# RGB_LED_BUCK_Converters.net
KiCad netlist of a schematic drawn in Altium Designer
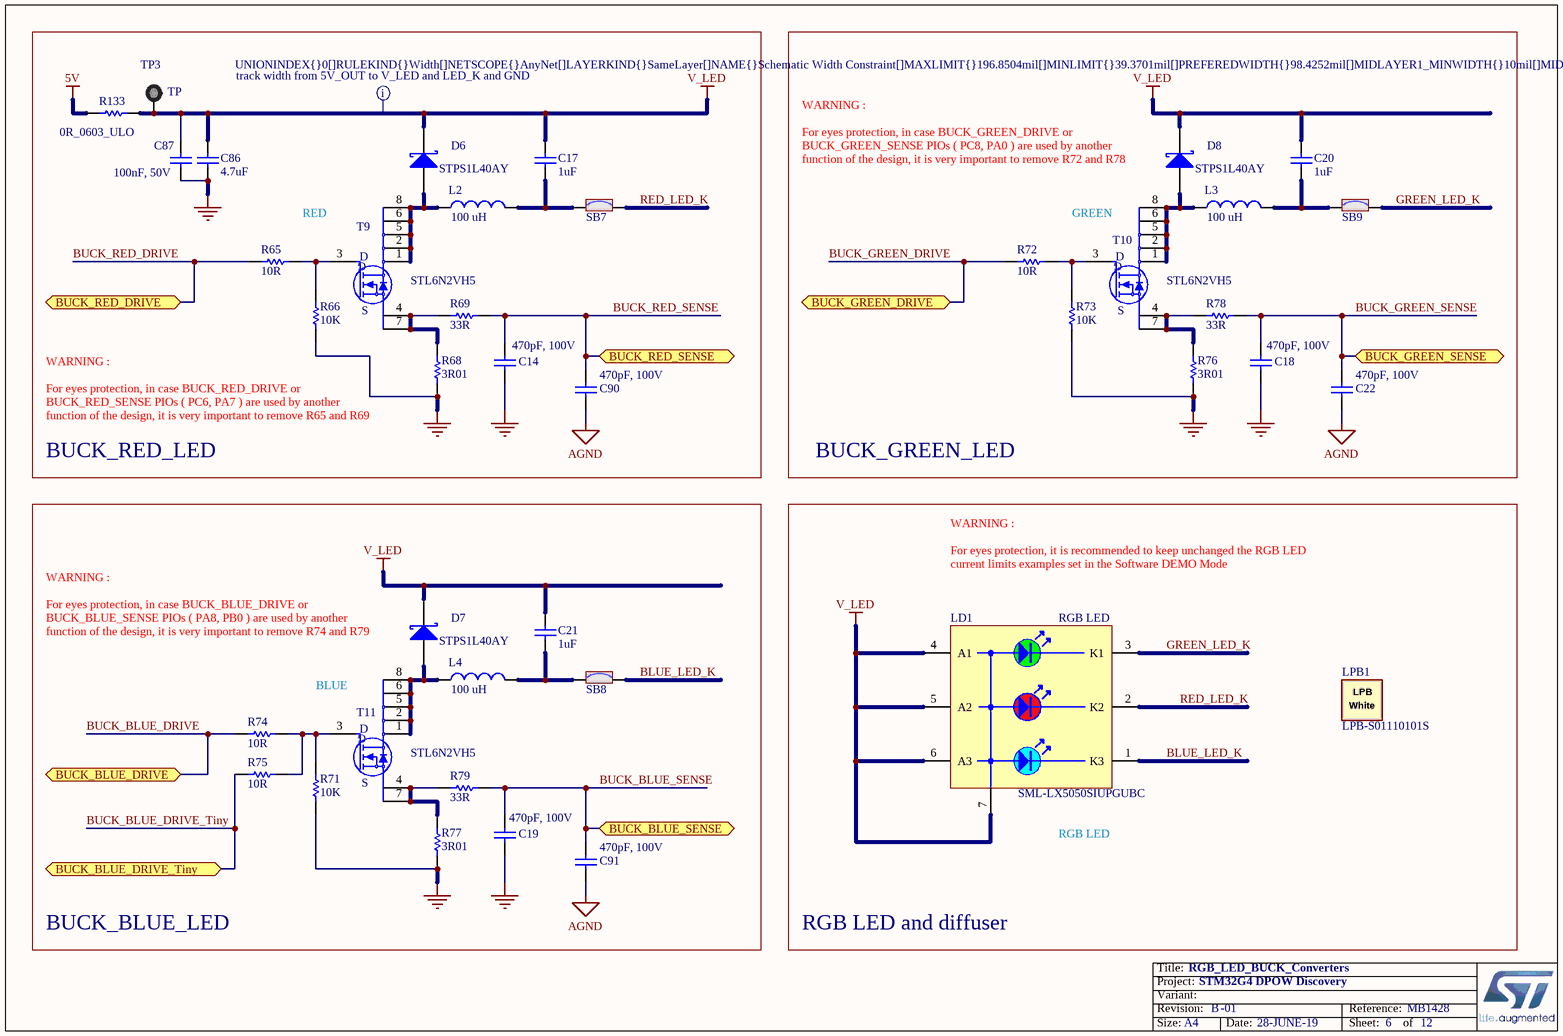
[diagram p0: RGB_LED_BUCK_Converters.SchDoc]

(export (version "E")
  (design (tool "Eeschema 10.0.6"))
  (components
    (comp (ref "C14")
      (value "470pF, 100V")
      (footprint "C0603_H0P8")
      (description "Capacitor, MLCC, 470pF, 100V, X7R, 10%, 0603, T=0.8mm")
      (fields
        (field (name "INTERNAL_PART_NUMBER") "MCD-01731")
        (field (name "MANUFACTURER_PART_NUMBER") "CC0603KRX7R0BB471")
        (field (name "PROVIDED_BY") "SUBCO")
      )
      (libsource (lib "MCD_PARTS_database") (part "Capacitor"))
    )
    (comp (ref "C17")
      (value "1uF")
      (footprint "C0805_H0P85")
      (description "Capacitor, MLCC, 1uF, 16V, X5R, 10%, 0805, T=0.85mm")
      (fields
        (field (name "INTERNAL_PART_NUMBER") "MCD-01550")
        (field (name "MANUFACTURER_PART_NUMBER") "CC0805KRX5R7BB105")
        (field (name "PROVIDED_BY") "SUBCO")
      )
      (libsource (lib "MCD_PARTS_database") (part "Capacitor"))
    )
    (comp (ref "C18")
      (value "470pF, 100V")
      (footprint "C0603_H0P8")
      (description "Capacitor, MLCC, 470pF, 100V, X7R, 10%, 0603, T=0.8mm")
      (fields
        (field (name "INTERNAL_PART_NUMBER") "MCD-01731")
        (field (name "MANUFACTURER_PART_NUMBER") "CC0603KRX7R0BB471")
        (field (name "PROVIDED_BY") "SUBCO")
      )
      (libsource (lib "MCD_PARTS_database") (part "Capacitor"))
    )
    (comp (ref "C19")
      (value "470pF, 100V")
      (footprint "C0603_H0P8")
      (description "Capacitor, MLCC, 470pF, 100V, X7R, 10%, 0603, T=0.8mm")
      (fields
        (field (name "INTERNAL_PART_NUMBER") "MCD-01731")
        (field (name "MANUFACTURER_PART_NUMBER") "CC0603KRX7R0BB471")
        (field (name "PROVIDED_BY") "SUBCO")
      )
      (libsource (lib "MCD_PARTS_database") (part "Capacitor"))
    )
    (comp (ref "C20")
      (value "1uF")
      (footprint "C0805_H0P85")
      (description "Capacitor, MLCC, 1uF, 16V, X5R, 10%, 0805, T=0.85mm")
      (fields
        (field (name "INTERNAL_PART_NUMBER") "MCD-01550")
        (field (name "MANUFACTURER_PART_NUMBER") "CC0805KRX5R7BB105")
        (field (name "PROVIDED_BY") "SUBCO")
      )
      (libsource (lib "MCD_PARTS_database") (part "Capacitor"))
    )
    (comp (ref "C21")
      (value "1uF")
      (footprint "C0805_H0P85")
      (description "Capacitor, MLCC, 1uF, 16V, X5R, 10%, 0805, T=0.85mm")
      (fields
        (field (name "INTERNAL_PART_NUMBER") "MCD-01550")
        (field (name "MANUFACTURER_PART_NUMBER") "CC0805KRX5R7BB105")
        (field (name "PROVIDED_BY") "SUBCO")
      )
      (libsource (lib "MCD_PARTS_database") (part "Capacitor"))
    )
    (comp (ref "C22")
      (value "470pF, 100V")
      (footprint "C0603_H0P8")
      (description "Capacitor, MLCC, 470pF, 100V, X7R, 10%, 0603, T=0.8mm")
      (fields
        (field (name "INTERNAL_PART_NUMBER") "MCD-01731")
        (field (name "MANUFACTURER_PART_NUMBER") "CC0603KRX7R0BB471")
        (field (name "PROVIDED_BY") "SUBCO")
      )
      (libsource (lib "MCD_PARTS_database") (part "Capacitor"))
    )
    (comp (ref "C86")
      (value "4.7uF")
      (footprint "C0603")
      (description "Capacitor, MLCC, 4.7uF, 16V, X5R, 10%, 0603, T=0.8mm")
      (fields
        (field (name "INTERNAL_PART_NUMBER") "MCD-00009")
        (field (name "MANUFACTURER_PART_NUMBER") "CC0603KRX5R7BB475")
        (field (name "PROVIDED_BY") "SUBCO")
      )
      (libsource (lib "MCD_PARTS_database") (part "Capacitor"))
    )
    (comp (ref "C87")
      (value "100nF, 50V")
      (footprint "C0805_H0P85")
      (description "Capacitor, MLCC, 100nF, 50V, X7R, 10%, 0805, T=0,85mm")
      (fields
        (field (name "INTERNAL_PART_NUMBER") "MCD-01525")
        (field (name "MANUFACTURER_PART_NUMBER") "CC0805KRX7R9BB104")
        (field (name "PROVIDED_BY") "SUBCO")
      )
      (libsource (lib "MCD_PARTS_database") (part "Capacitor"))
    )
    (comp (ref "C90")
      (value "470pF, 100V")
      (footprint "C0603_H0P8")
      (description "Capacitor, MLCC, 470pF, 100V, X7R, 10%, 0603, T=0.8mm")
      (fields
        (field (name "INTERNAL_PART_NUMBER") "MCD-01731")
        (field (name "MANUFACTURER_PART_NUMBER") "CC0603KRX7R0BB471")
        (field (name "PROVIDED_BY") "SUBCO")
      )
      (libsource (lib "MCD_PARTS_database") (part "Capacitor"))
    )
    (comp (ref "C91")
      (value "470pF, 100V")
      (footprint "C0603_H0P8")
      (description "Capacitor, MLCC, 470pF, 100V, X7R, 10%, 0603, T=0.8mm")
      (fields
        (field (name "INTERNAL_PART_NUMBER") "MCD-01731")
        (field (name "MANUFACTURER_PART_NUMBER") "CC0603KRX7R0BB471")
        (field (name "PROVIDED_BY") "SUBCO")
      )
      (libsource (lib "MCD_PARTS_database") (part "Capacitor"))
    )
    (comp (ref "D6")
      (value "STPS1L40AY")
      (footprint "DIO_SMA_1A_2K")
      (description "Low Drop power Schottky rectifier(1A, 40V, 0.37 V)")
      (fields
        (field (name "INTERNAL_PART_NUMBER") "MCD-00606")
        (field (name "MANUFACTURER") "STMICROELECTRONICS")
        (field (name "PROVIDED_BY") "SUBCO with ST control")
      )
      (libsource (lib "MCD_PARTS_database") (part "SCHOTTKY"))
    )
    (comp (ref "D7")
      (value "STPS1L40AY")
      (footprint "DIO_SMA_1A_2K")
      (description "Low Drop power Schottky rectifier(1A, 40V, 0.37 V)")
      (fields
        (field (name "INTERNAL_PART_NUMBER") "MCD-00606")
        (field (name "MANUFACTURER") "STMICROELECTRONICS")
        (field (name "PROVIDED_BY") "SUBCO with ST control")
      )
      (libsource (lib "MCD_PARTS_database") (part "SCHOTTKY"))
    )
    (comp (ref "D8")
      (value "STPS1L40AY")
      (footprint "DIO_SMA_1A_2K")
      (description "Low Drop power Schottky rectifier(1A, 40V, 0.37 V)")
      (fields
        (field (name "INTERNAL_PART_NUMBER") "MCD-00606")
        (field (name "MANUFACTURER") "STMICROELECTRONICS")
        (field (name "PROVIDED_BY") "SUBCO with ST control")
      )
      (libsource (lib "MCD_PARTS_database") (part "SCHOTTKY"))
    )
    (comp (ref "L2")
      (value "100 uH")
      (footprint "IND_SUNLORD_SWPA5040S")
      (description "SMD Wire wound power inductor, 100uH, 20%, Isat 0.9A, 560mohm, 5.0x5.0x4.0mm")
      (fields
        (field (name "INTERNAL_PART_NUMBER") "MCD-01734")
        (field (name "MANUFACTURER_PART_NUMBER") "SWPA5040S101MT")
        (field (name "PROVIDED_BY") "SUBCO")
      )
      (libsource (lib "MCD_PARTS_database") (part "Inductor"))
    )
    (comp (ref "L3")
      (value "100 uH")
      (footprint "IND_SUNLORD_SWPA5040S")
      (description "SMD Wire wound power inductor, 100uH, 20%, Isat 0.9A, 560mohm, 5.0x5.0x4.0mm")
      (fields
        (field (name "INTERNAL_PART_NUMBER") "MCD-01734")
        (field (name "MANUFACTURER_PART_NUMBER") "SWPA5040S101MT")
        (field (name "PROVIDED_BY") "SUBCO")
      )
      (libsource (lib "MCD_PARTS_database") (part "Inductor"))
    )
    (comp (ref "L4")
      (value "100 uH")
      (footprint "IND_SUNLORD_SWPA5040S")
      (description "SMD Wire wound power inductor, 100uH, 20%, Isat 0.9A, 560mohm, 5.0x5.0x4.0mm")
      (fields
        (field (name "INTERNAL_PART_NUMBER") "MCD-01734")
        (field (name "MANUFACTURER_PART_NUMBER") "SWPA5040S101MT")
        (field (name "PROVIDED_BY") "SUBCO")
      )
      (libsource (lib "MCD_PARTS_database") (part "Inductor"))
    )
    (comp (ref "LD1")
      (value "RGB LED")
      (footprint "LED_PLCC6-EPAD_LUMEX_SML-LX5050SIUPGUBC")
      (description "Mid Power RGB LED , SMD, 3x150 mA")
      (fields
        (field (name "INTERNAL_PART_NUMBER") "MCD-01580")
        (field (name "MANUFACTURER_PART_NUMBER") "SML-LX5050SIUPGUBC")
        (field (name "MANUFACTURER") "LUMEX")
        (field (name "PROVIDED_BY") "SUBCO")
      )
      (libsource (lib "MCD_PARTS_database") (part "LED_POWER_RGB"))
    )
    (comp (ref "LPB1")
      (value "LPB-S01110101S")
      (footprint "LIGHT_10MM-SQUARE-LIGHT-BAR_LUMEX_LPB-S01110101S")
      (description "10mm Square Light Bar.")
      (fields
        (field (name "INTERNAL_PART_NUMBER") "MCD-01191")
        (field (name "MANUFACTURER") "LUMEX")
        (field (name "PROVIDED_BY") "SUBCO")
      )
      (libsource (lib "MCD_PARTS_database") (part "LPB-S01110101S"))
    )
    (comp (ref "R65")
      (value "10R")
      (footprint "R0805_H0P5")
      (description "Resistor,10R,0805,1%, 1/8W")
      (fields
        (field (name "INTERNAL_PART_NUMBER") "MCD-01548")
        (field (name "MANUFACTURER_PART_NUMBER") "RC0805FR-0710RL")
        (field (name "PROVIDED_BY") "SUBCO")
      )
      (libsource (lib "MCD_PARTS_database") (part "Resistor"))
    )
    (comp (ref "R66")
      (value "10K")
      (footprint "R0805")
      (description "Resistor,10K,0805,1%,1/8W")
      (fields
        (field (name "INTERNAL_PART_NUMBER") "MCD-01154")
        (field (name "MANUFACTURER_PART_NUMBER") "RC0805FR-0710KL")
        (field (name "PROVIDED_BY") "SUBCO")
      )
      (libsource (lib "MCD_PARTS_database") (part "Resistor"))
    )
    (comp (ref "R68")
      (value "3R01")
      (footprint "R1206_H0P55")
      (description "Resistor, 3R01, 1206, 1%, 1/4W")
      (fields
        (field (name "INTERNAL_PART_NUMBER") "MCD-01528")
        (field (name "MANUFACTURER_PART_NUMBER") "RC1206FR-073R01L")
        (field (name "PROVIDED_BY") "SUBCO")
      )
      (libsource (lib "MCD_PARTS_database") (part "Resistor"))
    )
    (comp (ref "R69")
      (value "33R")
      (footprint "R0603")
      (description "Resistor,33R,0603,1%,1/10W")
      (fields
        (field (name "INTERNAL_PART_NUMBER") "MCD-00456")
        (field (name "MANUFACTURER_PART_NUMBER") "RC0603FR-0733RL")
        (field (name "PROVIDED_BY") "SUBCO")
      )
      (libsource (lib "MCD_PARTS_database") (part "Resistor"))
    )
    (comp (ref "R71")
      (value "10K")
      (footprint "R0805")
      (description "Resistor,10K,0805,1%,1/8W")
      (fields
        (field (name "INTERNAL_PART_NUMBER") "MCD-01154")
        (field (name "MANUFACTURER_PART_NUMBER") "RC0805FR-0710KL")
        (field (name "PROVIDED_BY") "SUBCO")
      )
      (libsource (lib "MCD_PARTS_database") (part "Resistor"))
    )
    (comp (ref "R72")
      (value "10R")
      (footprint "R0805_H0P5")
      (description "Resistor,10R,0805,1%, 1/8W")
      (fields
        (field (name "INTERNAL_PART_NUMBER") "MCD-01548")
        (field (name "MANUFACTURER_PART_NUMBER") "RC0805FR-0710RL")
        (field (name "PROVIDED_BY") "SUBCO")
      )
      (libsource (lib "MCD_PARTS_database") (part "Resistor"))
    )
    (comp (ref "R73")
      (value "10K")
      (footprint "R0805")
      (description "Resistor,10K,0805,1%,1/8W")
      (fields
        (field (name "INTERNAL_PART_NUMBER") "MCD-01154")
        (field (name "MANUFACTURER_PART_NUMBER") "RC0805FR-0710KL")
        (field (name "PROVIDED_BY") "SUBCO")
      )
      (libsource (lib "MCD_PARTS_database") (part "Resistor"))
    )
    (comp (ref "R74")
      (value "10R")
      (footprint "R0805_H0P5")
      (description "Resistor,10R,0805,1%, 1/8W")
      (fields
        (field (name "INTERNAL_PART_NUMBER") "MCD-01548")
        (field (name "MANUFACTURER_PART_NUMBER") "RC0805FR-0710RL")
        (field (name "PROVIDED_BY") "SUBCO")
      )
      (libsource (lib "MCD_PARTS_database") (part "Resistor"))
    )
    (comp (ref "R75")
      (value "10R")
      (footprint "R0805_H0P5")
      (description "Resistor,10R,0805,1%, 1/8W")
      (fields
        (field (name "INTERNAL_PART_NUMBER") "MCD-01548")
        (field (name "MANUFACTURER_PART_NUMBER") "RC0805FR-0710RL")
        (field (name "PROVIDED_BY") "SUBCO")
      )
      (libsource (lib "MCD_PARTS_database") (part "Resistor"))
    )
    (comp (ref "R76")
      (value "3R01")
      (footprint "R1206_H0P55")
      (description "Resistor, 3R01, 1206, 1%, 1/4W")
      (fields
        (field (name "INTERNAL_PART_NUMBER") "MCD-01528")
        (field (name "MANUFACTURER_PART_NUMBER") "RC1206FR-073R01L")
        (field (name "PROVIDED_BY") "SUBCO")
      )
      (libsource (lib "MCD_PARTS_database") (part "Resistor"))
    )
    (comp (ref "R77")
      (value "3R01")
      (footprint "R1206_H0P55")
      (description "Resistor, 3R01, 1206, 1%, 1/4W")
      (fields
        (field (name "INTERNAL_PART_NUMBER") "MCD-01528")
        (field (name "MANUFACTURER_PART_NUMBER") "RC1206FR-073R01L")
        (field (name "PROVIDED_BY") "SUBCO")
      )
      (libsource (lib "MCD_PARTS_database") (part "Resistor"))
    )
    (comp (ref "R78")
      (value "33R")
      (footprint "R0603")
      (description "Resistor,33R,0603,1%,1/10W")
      (fields
        (field (name "INTERNAL_PART_NUMBER") "MCD-00456")
        (field (name "MANUFACTURER_PART_NUMBER") "RC0603FR-0733RL")
        (field (name "PROVIDED_BY") "SUBCO")
      )
      (libsource (lib "MCD_PARTS_database") (part "Resistor"))
    )
    (comp (ref "R79")
      (value "33R")
      (footprint "R0603")
      (description "Resistor,33R,0603,1%,1/10W")
      (fields
        (field (name "INTERNAL_PART_NUMBER") "MCD-00456")
        (field (name "MANUFACTURER_PART_NUMBER") "RC0603FR-0733RL")
        (field (name "PROVIDED_BY") "SUBCO")
      )
      (libsource (lib "MCD_PARTS_database") (part "Resistor"))
    )
    (comp (ref "R133")
      (value "0R_0603_ULO")
      (footprint "R0603")
      (description "Resistor,0R,0603,ULO")
      (fields
        (field (name "INTERNAL_PART_NUMBER") "MCD-00181")
        (field (name "MANUFACTURER_PART_NUMBER") "PMR03EZPJ000")
        (field (name "PROVIDED_BY") "SUBCO")
      )
      (libsource (lib "MCD_PARTS_database") (part "Resistor"))
    )
    (comp (ref "SB7")
      (value "~")
      (footprint "SOLDER-BRIDGE_R0603-0R")
      (description "Solder Bridge ON")
      (fields
        (field (name "INTERNAL_PART_NUMBER") "MCD-00071")
        (field (name "MANUFACTURER_PART_NUMBER") "RC0603JR-070RL")
        (field (name "PROVIDED_BY") "SUBCO")
      )
      (libsource (lib "MCD_PARTS_database") (part "SB_ON"))
    )
    (comp (ref "SB8")
      (value "~")
      (footprint "SOLDER-BRIDGE_R0603-0R")
      (description "Solder Bridge ON")
      (fields
        (field (name "INTERNAL_PART_NUMBER") "MCD-00071")
        (field (name "MANUFACTURER_PART_NUMBER") "RC0603JR-070RL")
        (field (name "PROVIDED_BY") "SUBCO")
      )
      (libsource (lib "MCD_PARTS_database") (part "SB_ON"))
    )
    (comp (ref "SB9")
      (value "~")
      (footprint "SOLDER-BRIDGE_R0603-0R")
      (description "Solder Bridge ON")
      (fields
        (field (name "INTERNAL_PART_NUMBER") "MCD-00071")
        (field (name "MANUFACTURER_PART_NUMBER") "RC0603JR-070RL")
        (field (name "PROVIDED_BY") "SUBCO")
      )
      (libsource (lib "MCD_PARTS_database") (part "SB_ON"))
    )
    (comp (ref "T9")
      (value "STL6N2VH5")
      (footprint "MOS_POWERFLAT_2X2_P065")
      (description "N-channel 20 V, 0.025 O typ., 6 A STripFET™ V Power MOSFET in a PowerFLAT™ 2x2 package")
      (fields
        (field (name "INTERNAL_PART_NUMBER") "MCD-01028")
        (field (name "MANUFACTURER") "STMICROELECTRONICS")
        (field (name "PROVIDED_BY") "SUBCO with ST control")
      )
      (libsource (lib "MCD_PARTS_database") (part "STL6N2VH5"))
    )
    (comp (ref "T10")
      (value "STL6N2VH5")
      (footprint "MOS_POWERFLAT_2X2_P065")
      (description "N-channel 20 V, 0.025 O typ., 6 A STripFET™ V Power MOSFET in a PowerFLAT™ 2x2 package")
      (fields
        (field (name "INTERNAL_PART_NUMBER") "MCD-01028")
        (field (name "MANUFACTURER") "STMICROELECTRONICS")
        (field (name "PROVIDED_BY") "SUBCO with ST control")
      )
      (libsource (lib "MCD_PARTS_database") (part "STL6N2VH5"))
    )
    (comp (ref "T11")
      (value "STL6N2VH5")
      (footprint "MOS_POWERFLAT_2X2_P065")
      (description "N-channel 20 V, 0.025 O typ., 6 A STripFET™ V Power MOSFET in a PowerFLAT™ 2x2 package")
      (fields
        (field (name "INTERNAL_PART_NUMBER") "MCD-01028")
        (field (name "MANUFACTURER") "STMICROELECTRONICS")
        (field (name "PROVIDED_BY") "SUBCO with ST control")
      )
      (libsource (lib "MCD_PARTS_database") (part "STL6N2VH5"))
    )
    (comp (ref "TP3")
      (value "TP")
      (footprint "TP_PTH_1MM_2MM")
      (description "Test Point trought hole 1mm/2mm")
      (fields
        (field (name "INTERNAL_PART_NUMBER") "MCD-01506")
        (field (name "MANUFACTURER_PART_NUMBER") "n/a")
      )
      (libsource (lib "MCD_PARTS_database") (part "Test_Point_PTH_1mm_2mm"))
    )
  )
  (nets
    (net (code "1") (name "/BLUE_LED_K") (class "Default")
      (node (ref "LD1") (pin "1") (pinfunction "K3_1") (pintype "passive"))
      (node (ref "SB8") (pin "2") (pinfunction "2_2") (pintype "passive"))
    )
    (net (code "2") (name "/BUCK_BLUE_DRIVE") (class "Default")
      (node (ref "R74") (pin "1") (pinfunction "1_1") (pintype "passive"))
    )
    (net (code "3") (name "/BUCK_BLUE_DRIVE_Tiny") (class "Default")
      (node (ref "R75") (pin "1") (pinfunction "1_1") (pintype "passive"))
    )
    (net (code "4") (name "/BUCK_BLUE_SENSE") (class "Default")
      (node (ref "C19") (pin "2") (pinfunction "2_2") (pintype "passive"))
      (node (ref "C91") (pin "2") (pinfunction "2_2") (pintype "passive"))
      (node (ref "R79") (pin "2") (pinfunction "2_2") (pintype "passive"))
    )
    (net (code "5") (name "/BUCK_GREEN_DRIVE") (class "Default")
      (node (ref "R72") (pin "1") (pinfunction "1_1") (pintype "passive"))
    )
    (net (code "6") (name "/BUCK_GREEN_SENSE") (class "Default")
      (node (ref "C18") (pin "2") (pinfunction "2_2") (pintype "passive"))
      (node (ref "C22") (pin "2") (pinfunction "2_2") (pintype "passive"))
      (node (ref "R78") (pin "2") (pinfunction "2_2") (pintype "passive"))
    )
    (net (code "7") (name "/BUCK_RED_DRIVE") (class "Default")
      (node (ref "R65") (pin "1") (pinfunction "1_1") (pintype "passive"))
    )
    (net (code "8") (name "/BUCK_RED_SENSE") (class "Default")
      (node (ref "C14") (pin "2") (pinfunction "2_2") (pintype "passive"))
      (node (ref "C90") (pin "2") (pinfunction "2_2") (pintype "passive"))
      (node (ref "R69") (pin "2") (pinfunction "2_2") (pintype "passive"))
    )
    (net (code "9") (name "/GREEN_LED_K") (class "Default")
      (node (ref "LD1") (pin "3") (pinfunction "K1_3") (pintype "passive"))
      (node (ref "SB9") (pin "2") (pinfunction "2_2") (pintype "passive"))
    )
    (net (code "10") (name "/RED_LED_K") (class "Default")
      (node (ref "LD1") (pin "2") (pinfunction "K2_2") (pintype "passive"))
      (node (ref "SB7") (pin "2") (pinfunction "2_2") (pintype "passive"))
    )
    (net (code "11") (name "5V") (class "Default")
      (node (ref "R133") (pin "1") (pinfunction "1_1") (pintype "passive"))
    )
    (net (code "12") (name "AGND") (class "Default")
      (node (ref "C22") (pin "1") (pinfunction "1_1") (pintype "passive"))
      (node (ref "C90") (pin "1") (pinfunction "1_1") (pintype "passive"))
      (node (ref "C91") (pin "1") (pinfunction "1_1") (pintype "passive"))
    )
    (net (code "13") (name "GND") (class "Default")
      (node (ref "C14") (pin "1") (pinfunction "1_1") (pintype "passive"))
      (node (ref "C18") (pin "1") (pinfunction "1_1") (pintype "passive"))
      (node (ref "C19") (pin "1") (pinfunction "1_1") (pintype "passive"))
      (node (ref "C86") (pin "1") (pinfunction "1_1") (pintype "passive"))
      (node (ref "C87") (pin "1") (pinfunction "1_1") (pintype "passive"))
      (node (ref "R66") (pin "1") (pinfunction "1_1") (pintype "passive"))
      (node (ref "R68") (pin "1") (pinfunction "1_1") (pintype "passive"))
      (node (ref "R71") (pin "1") (pinfunction "1_1") (pintype "passive"))
      (node (ref "R73") (pin "1") (pinfunction "1_1") (pintype "passive"))
      (node (ref "R76") (pin "1") (pinfunction "1_1") (pintype "passive"))
      (node (ref "R77") (pin "1") (pinfunction "1_1") (pintype "passive"))
    )
    (net (code "14") (name "Net-(C17-Pad1)") (class "Default")
      (node (ref "C17") (pin "1") (pinfunction "1_1") (pintype "passive"))
      (node (ref "L2") (pin "2") (pinfunction "2_2") (pintype "passive"))
      (node (ref "SB7") (pin "1") (pinfunction "1_1") (pintype "passive"))
    )
    (net (code "15") (name "Net-(C20-Pad1)") (class "Default")
      (node (ref "C20") (pin "1") (pinfunction "1_1") (pintype "passive"))
      (node (ref "L3") (pin "2") (pinfunction "2_2") (pintype "passive"))
      (node (ref "SB9") (pin "1") (pinfunction "1_1") (pintype "passive"))
    )
    (net (code "16") (name "Net-(C21-Pad1)") (class "Default")
      (node (ref "C21") (pin "1") (pinfunction "1_1") (pintype "passive"))
      (node (ref "L4") (pin "2") (pinfunction "2_2") (pintype "passive"))
      (node (ref "SB8") (pin "1") (pinfunction "1_1") (pintype "passive"))
    )
    (net (code "17") (name "Net-(D6-A)") (class "Default")
      (node (ref "D6") (pin "1") (pinfunction "A_1") (pintype "passive"))
      (node (ref "L2") (pin "1") (pinfunction "1_1") (pintype "passive"))
      (node (ref "T9") (pin "1") (pinfunction "D_1") (pintype "passive"))
      (node (ref "T9") (pin "2") (pinfunction "D_2") (pintype "passive"))
      (node (ref "T9") (pin "5") (pinfunction "D_5") (pintype "passive"))
      (node (ref "T9") (pin "6") (pinfunction "D_6") (pintype "passive"))
      (node (ref "T9") (pin "8") (pinfunction "D_8") (pintype "passive"))
    )
    (net (code "18") (name "Net-(D7-A)") (class "Default")
      (node (ref "D7") (pin "1") (pinfunction "A_1") (pintype "passive"))
      (node (ref "L4") (pin "1") (pinfunction "1_1") (pintype "passive"))
      (node (ref "T11") (pin "1") (pinfunction "D_1") (pintype "passive"))
      (node (ref "T11") (pin "2") (pinfunction "D_2") (pintype "passive"))
      (node (ref "T11") (pin "5") (pinfunction "D_5") (pintype "passive"))
      (node (ref "T11") (pin "6") (pinfunction "D_6") (pintype "passive"))
      (node (ref "T11") (pin "8") (pinfunction "D_8") (pintype "passive"))
    )
    (net (code "19") (name "Net-(D8-A)") (class "Default")
      (node (ref "D8") (pin "1") (pinfunction "A_1") (pintype "passive"))
      (node (ref "L3") (pin "1") (pinfunction "1_1") (pintype "passive"))
      (node (ref "T10") (pin "1") (pinfunction "D_1") (pintype "passive"))
      (node (ref "T10") (pin "2") (pinfunction "D_2") (pintype "passive"))
      (node (ref "T10") (pin "5") (pinfunction "D_5") (pintype "passive"))
      (node (ref "T10") (pin "6") (pinfunction "D_6") (pintype "passive"))
      (node (ref "T10") (pin "8") (pinfunction "D_8") (pintype "passive"))
    )
    (net (code "20") (name "Net-(R68-Pad2)") (class "Default")
      (node (ref "R68") (pin "2") (pinfunction "2_2") (pintype "passive"))
      (node (ref "R69") (pin "1") (pinfunction "1_1") (pintype "passive"))
      (node (ref "T9") (pin "4") (pinfunction "S_4") (pintype "passive"))
      (node (ref "T9") (pin "7") (pinfunction "S_7") (pintype "passive"))
    )
    (net (code "21") (name "Net-(R76-Pad2)") (class "Default")
      (node (ref "R76") (pin "2") (pinfunction "2_2") (pintype "passive"))
      (node (ref "R78") (pin "1") (pinfunction "1_1") (pintype "passive"))
      (node (ref "T10") (pin "4") (pinfunction "S_4") (pintype "passive"))
      (node (ref "T10") (pin "7") (pinfunction "S_7") (pintype "passive"))
    )
    (net (code "22") (name "Net-(R77-Pad2)") (class "Default")
      (node (ref "R77") (pin "2") (pinfunction "2_2") (pintype "passive"))
      (node (ref "R79") (pin "1") (pinfunction "1_1") (pintype "passive"))
      (node (ref "T11") (pin "4") (pinfunction "S_4") (pintype "passive"))
      (node (ref "T11") (pin "7") (pinfunction "S_7") (pintype "passive"))
    )
    (net (code "23") (name "Net-(T9-G)") (class "Default")
      (node (ref "R65") (pin "2") (pinfunction "2_2") (pintype "passive"))
      (node (ref "R66") (pin "2") (pinfunction "2_2") (pintype "passive"))
      (node (ref "T9") (pin "3") (pinfunction "G_3") (pintype "passive"))
    )
    (net (code "24") (name "Net-(T10-G)") (class "Default")
      (node (ref "R72") (pin "2") (pinfunction "2_2") (pintype "passive"))
      (node (ref "R73") (pin "2") (pinfunction "2_2") (pintype "passive"))
      (node (ref "T10") (pin "3") (pinfunction "G_3") (pintype "passive"))
    )
    (net (code "25") (name "Net-(T11-G)") (class "Default")
      (node (ref "R71") (pin "2") (pinfunction "2_2") (pintype "passive"))
      (node (ref "R74") (pin "2") (pinfunction "2_2") (pintype "passive"))
      (node (ref "R75") (pin "2") (pinfunction "2_2") (pintype "passive"))
      (node (ref "T11") (pin "3") (pinfunction "G_3") (pintype "passive"))
    )
    (net (code "26") (name "V_LED") (class "Default")
      (node (ref "C17") (pin "2") (pinfunction "2_2") (pintype "passive"))
      (node (ref "C20") (pin "2") (pinfunction "2_2") (pintype "passive"))
      (node (ref "C21") (pin "2") (pinfunction "2_2") (pintype "passive"))
      (node (ref "C86") (pin "2") (pinfunction "2_2") (pintype "passive"))
      (node (ref "C87") (pin "2") (pinfunction "2_2") (pintype "passive"))
      (node (ref "D6") (pin "2") (pinfunction "K_2") (pintype "passive"))
      (node (ref "D7") (pin "2") (pinfunction "K_2") (pintype "passive"))
      (node (ref "D8") (pin "2") (pinfunction "K_2") (pintype "passive"))
      (node (ref "LD1") (pin "4") (pinfunction "A1_4") (pintype "passive"))
      (node (ref "LD1") (pin "5") (pinfunction "A2_5") (pintype "passive"))
      (node (ref "LD1") (pin "6") (pinfunction "A3_6") (pintype "passive"))
      (node (ref "LD1") (pin "7") (pinfunction "SLUG_7") (pintype "passive"))
      (node (ref "R133") (pin "2") (pinfunction "2_2") (pintype "passive"))
      (node (ref "TP3") (pin "1") (pinfunction "1_1") (pintype "passive"))
    )
  )
)
